# untitled.net
KiCad netlist of a schematic drawn in EAGLE
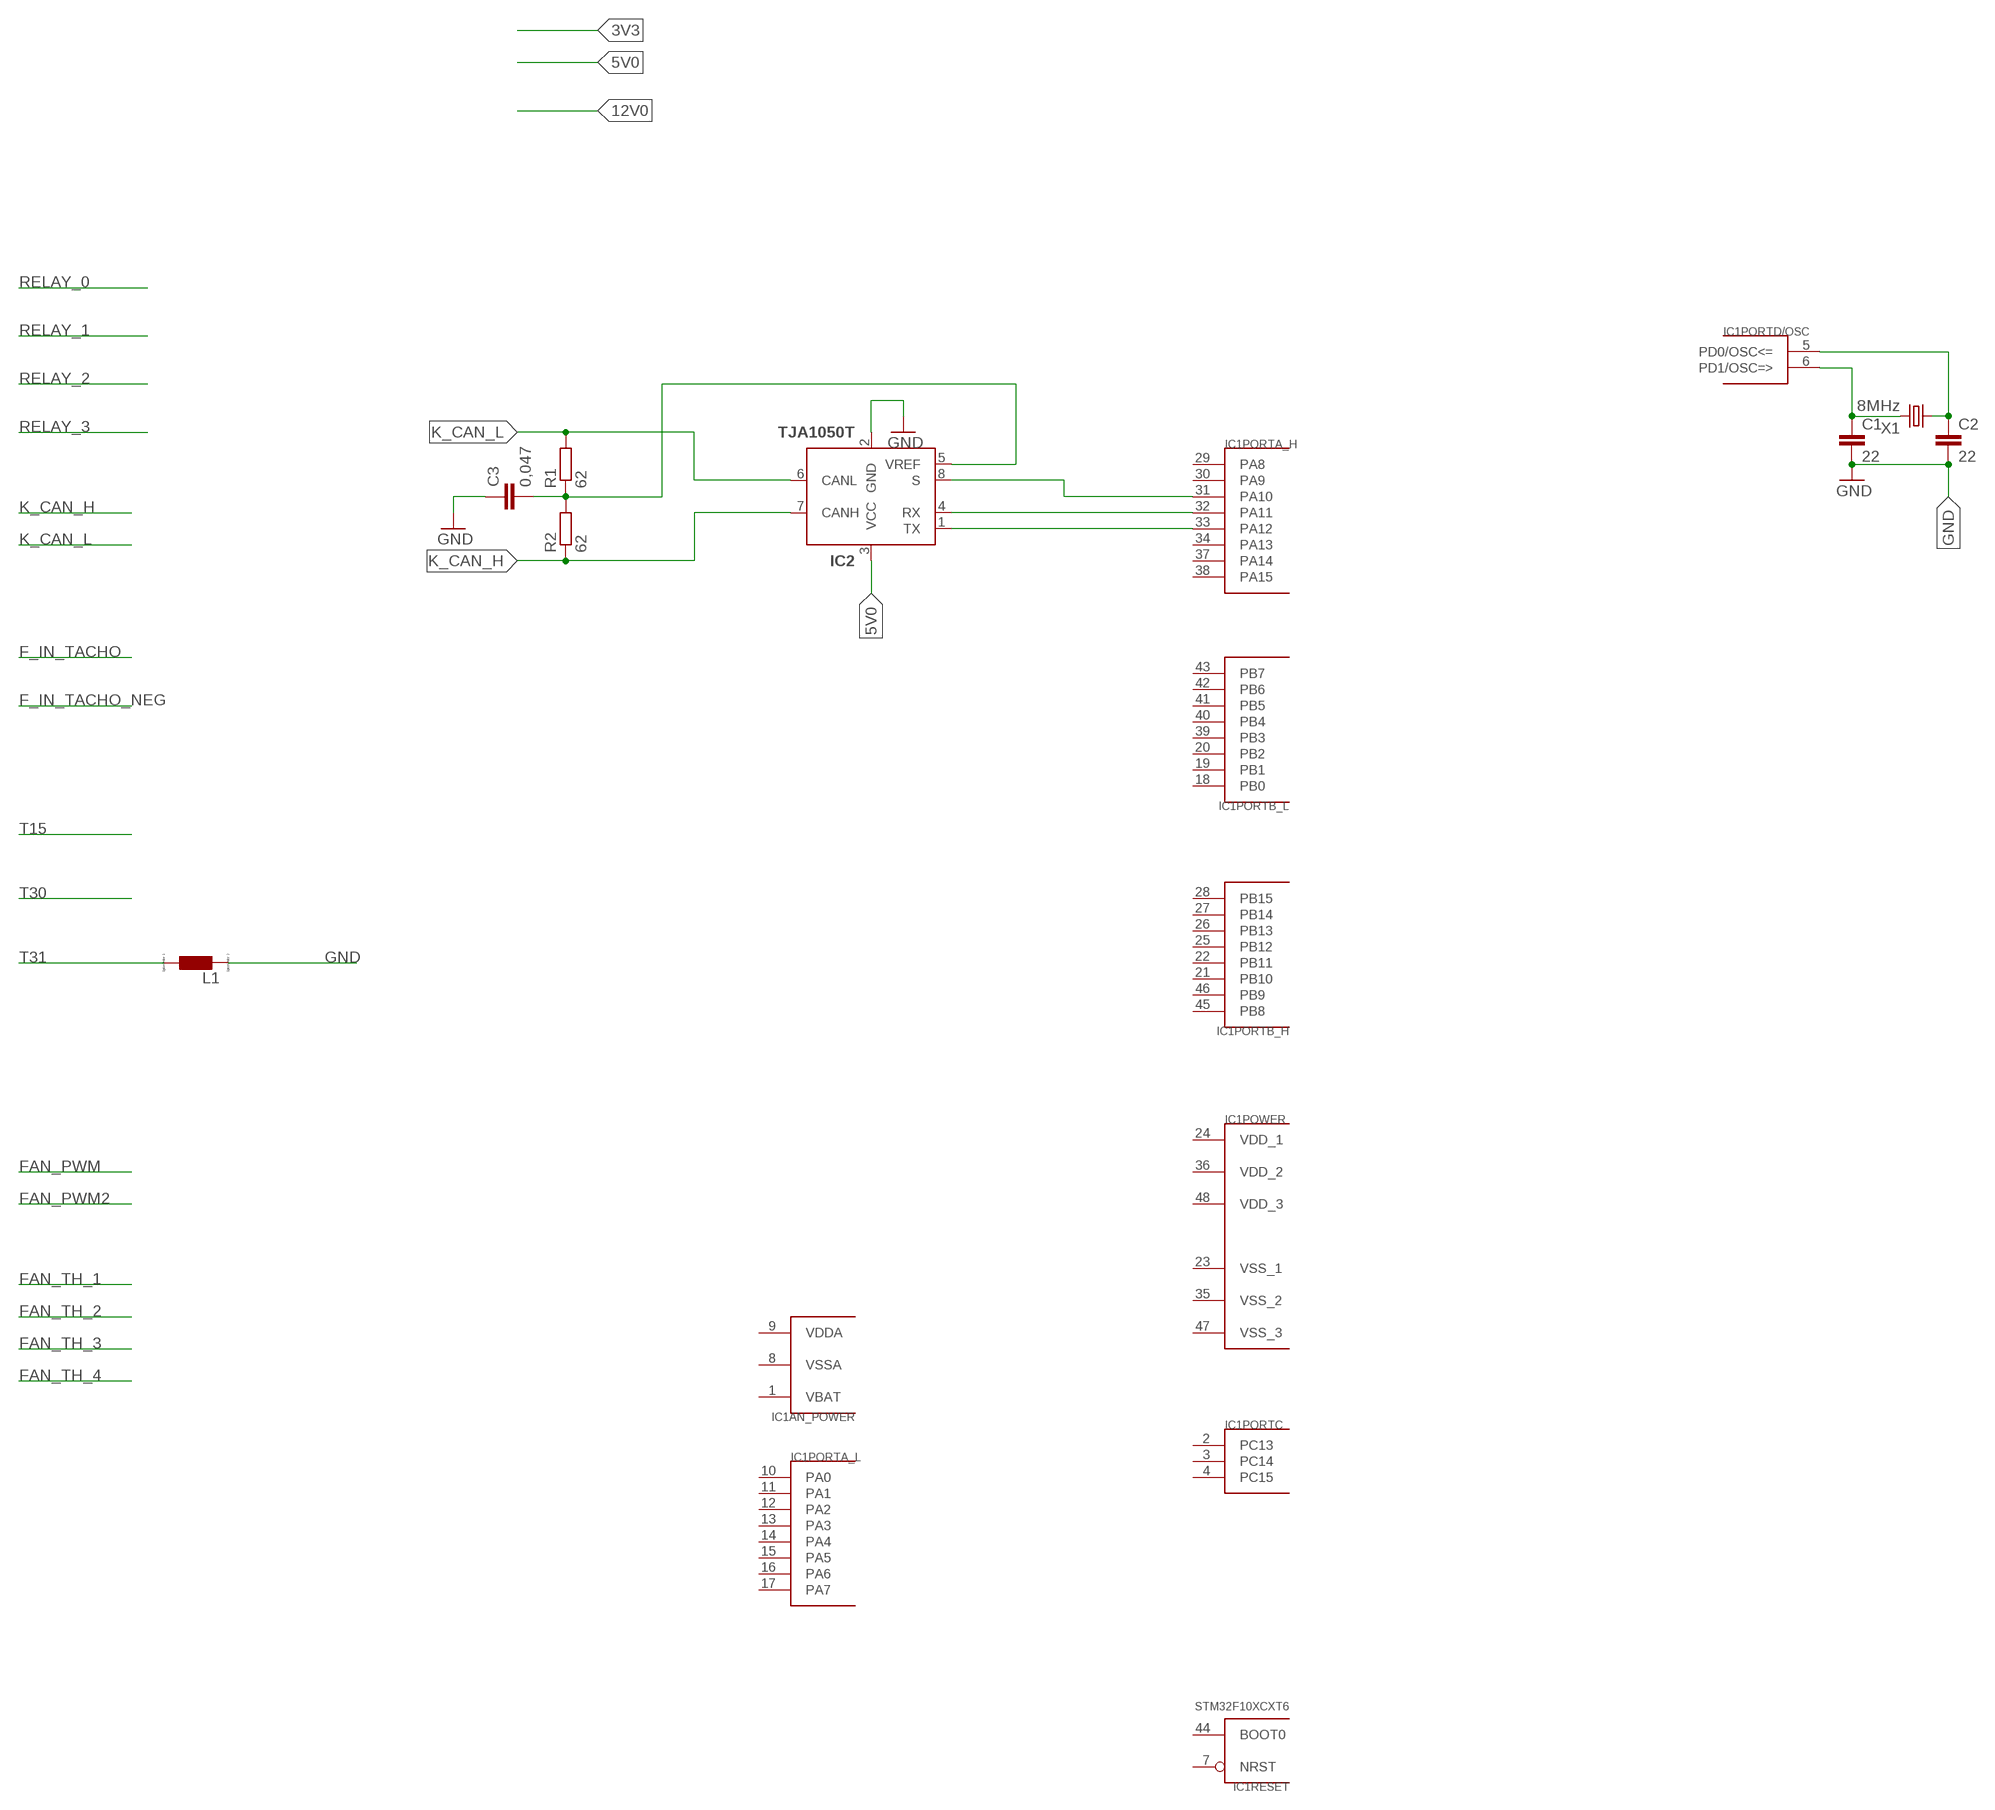
[diagram p0: schematic, sheet 1]

(export (version "E")
  (design (tool "Eeschema 10.0.6"))
  (components
    (comp (ref "C1")
      (value "22")
      (footprint "eagle-import:C0805")
      (libsource (lib "eagle-import") (part "C-EUC0805"))
    )
    (comp (ref "C2")
      (value "22")
      (footprint "eagle-import:C0805")
      (libsource (lib "eagle-import") (part "C-EUC0805"))
    )
    (comp (ref "C3")
      (value "0,047")
      (footprint "eagle-import:C0805")
      (libsource (lib "eagle-import") (part "C-EUC0805"))
    )
    (comp (ref "IC1")
      (value "STM32F10XCXT6")
      (footprint "eagle-import:TQFP48")
      (libsource (lib "eagle-import") (part "STM32F10XCXT6"))
    )
    (comp (ref "IC2")
      (value "TJA1050T")
      (footprint "eagle-import:SOIC8")
      (fields (field (name "MF") "NXP"))
      (libsource (lib "eagle-import") (part "TJA1050T"))
    )
    (comp (ref "L1")
      (value "L0204/7")
      (footprint "eagle-import:0204_7")
      (libsource (lib "eagle-import") (part "L0204/7"))
    )
    (comp (ref "R1")
      (value "62")
      (footprint "eagle-import:M0805")
      (libsource (lib "eagle-import") (part "R-EU_M0805"))
    )
    (comp (ref "R2")
      (value "62")
      (footprint "eagle-import:M0805")
      (libsource (lib "eagle-import") (part "R-EU_M0805"))
    )
    (comp (ref "X1")
      (value "8MHz")
      (footprint "eagle-import:HC49")
      (libsource (lib "eagle-import") (part "CRYSTALS-NOGND-HC49"))
    )
  )
  (nets
    (net (code "15") (name "/T31") (class "Default")
      (node (ref "L1") (pin "1") (pinfunction "1_1") (pintype "passive"))
    )
    (net (code "16") (name "/VBAT") (class "Default")
      (node (ref "IC1") (pin "1") (pinfunction "VBAT_1") (pintype "power_in"))
    )
    (net (code "17") (name "/VDDA") (class "Default")
      (node (ref "IC1") (pin "9") (pinfunction "VDDA_9") (pintype "power_in"))
    )
    (net (code "18") (name "/VDD_1") (class "Default")
      (node (ref "IC1") (pin "24") (pinfunction "VDD_1_24") (pintype "power_in"))
    )
    (net (code "19") (name "/VDD_2") (class "Default")
      (node (ref "IC1") (pin "36") (pinfunction "VDD_2_36") (pintype "power_in"))
    )
    (net (code "20") (name "/VDD_3") (class "Default")
      (node (ref "IC1") (pin "48") (pinfunction "VDD_3_48") (pintype "power_in"))
    )
    (net (code "21") (name "/VSSA") (class "Default")
      (node (ref "IC1") (pin "8") (pinfunction "VSSA_8") (pintype "power_in"))
    )
    (net (code "22") (name "/VSS_1") (class "Default")
      (node (ref "IC1") (pin "23") (pinfunction "VSS_1_23") (pintype "power_in"))
    )
    (net (code "23") (name "/VSS_2") (class "Default")
      (node (ref "IC1") (pin "35") (pinfunction "VSS_2_35") (pintype "power_in"))
    )
    (net (code "24") (name "/VSS_3") (class "Default")
      (node (ref "IC1") (pin "47") (pinfunction "VSS_3_47") (pintype "power_in"))
    )
    (net (code "26") (name "5V0") (class "Default")
      (node (ref "IC2") (pin "3") (pinfunction "VCC_3") (pintype "input"))
    )
    (net (code "28") (name "GND") (class "Default")
      (node (ref "C1") (pin "2") (pinfunction "2_2") (pintype "passive"))
      (node (ref "C2") (pin "2") (pinfunction "2_2") (pintype "passive"))
      (node (ref "C3") (pin "1") (pinfunction "1_1") (pintype "passive"))
      (node (ref "IC2") (pin "2") (pinfunction "GND_2") (pintype "power_in"))
      (node (ref "L1") (pin "2") (pinfunction "2_2") (pintype "passive"))
    )
    (net (code "29") (name "K_CAN_H") (class "Default")
      (node (ref "IC2") (pin "7") (pinfunction "CANH_7") (pintype "bidirectional"))
      (node (ref "R2") (pin "1") (pinfunction "1_1") (pintype "passive"))
    )
    (net (code "30") (name "K_CAN_L") (class "Default")
      (node (ref "IC2") (pin "6") (pinfunction "CANL_6") (pintype "bidirectional"))
      (node (ref "R1") (pin "2") (pinfunction "2_2") (pintype "passive"))
    )
    (net (code "31") (name "Net-(IC1B-PA10)") (class "Default")
      (node (ref "IC1") (pin "31") (pinfunction "PA10_31") (pintype "bidirectional"))
      (node (ref "IC2") (pin "8") (pinfunction "S_8") (pintype "input"))
    )
    (net (code "32") (name "Net-(IC1B-PA11)") (class "Default")
      (node (ref "IC1") (pin "32") (pinfunction "PA11_32") (pintype "bidirectional"))
      (node (ref "IC2") (pin "4") (pinfunction "RX_4") (pintype "output"))
    )
    (net (code "33") (name "Net-(IC1B-PA12)") (class "Default")
      (node (ref "IC1") (pin "33") (pinfunction "PA12_33") (pintype "bidirectional"))
      (node (ref "IC2") (pin "1") (pinfunction "TX_1") (pintype "input"))
    )
    (net (code "34") (name "Net-(IC1G-PD0{slash}OSC<=)") (class "Default")
      (node (ref "C2") (pin "1") (pinfunction "1_1") (pintype "passive"))
      (node (ref "IC1") (pin "5") (pinfunction "PD0/OSC<=_5") (pintype "bidirectional"))
      (node (ref "X1") (pin "1") (pinfunction "1_1") (pintype "passive"))
    )
    (net (code "35") (name "Net-(IC1G-PD1{slash}OSC=>)") (class "Default")
      (node (ref "C1") (pin "1") (pinfunction "1_1") (pintype "passive"))
      (node (ref "IC1") (pin "6") (pinfunction "PD1/OSC=>_6") (pintype "bidirectional"))
      (node (ref "X1") (pin "2") (pinfunction "2_2") (pintype "passive"))
    )
    (net (code "36") (name "Net-(IC2-VREF)") (class "Default")
      (node (ref "C3") (pin "2") (pinfunction "2_2") (pintype "passive"))
      (node (ref "IC2") (pin "5") (pinfunction "VREF_5") (pintype "output"))
      (node (ref "R1") (pin "1") (pinfunction "1_1") (pintype "passive"))
      (node (ref "R2") (pin "2") (pinfunction "2_2") (pintype "passive"))
    )
    (net (code "37") (name "unconnected-(IC1B-PA8-Pad29)") (class "Default")
      (node (ref "IC1") (pin "29") (pinfunction "PA8_29") (pintype "bidirectional"))
    )
    (net (code "38") (name "unconnected-(IC1B-PA9-Pad30)") (class "Default")
      (node (ref "IC1") (pin "30") (pinfunction "PA9_30") (pintype "bidirectional"))
    )
    (net (code "39") (name "unconnected-(IC1B-PA13-Pad34)") (class "Default")
      (node (ref "IC1") (pin "34") (pinfunction "PA13_34") (pintype "bidirectional"))
    )
    (net (code "40") (name "unconnected-(IC1B-PA14-Pad37)") (class "Default")
      (node (ref "IC1") (pin "37") (pinfunction "PA14_37") (pintype "bidirectional"))
    )
    (net (code "41") (name "unconnected-(IC1B-PA15-Pad38)") (class "Default")
      (node (ref "IC1") (pin "38") (pinfunction "PA15_38") (pintype "bidirectional"))
    )
    (net (code "42") (name "unconnected-(IC1C-PA0-Pad10)") (class "Default")
      (node (ref "IC1") (pin "10") (pinfunction "PA0_10") (pintype "bidirectional"))
    )
    (net (code "43") (name "unconnected-(IC1C-PA1-Pad11)") (class "Default")
      (node (ref "IC1") (pin "11") (pinfunction "PA1_11") (pintype "bidirectional"))
    )
    (net (code "44") (name "unconnected-(IC1C-PA2-Pad12)") (class "Default")
      (node (ref "IC1") (pin "12") (pinfunction "PA2_12") (pintype "bidirectional"))
    )
    (net (code "45") (name "unconnected-(IC1C-PA3-Pad13)") (class "Default")
      (node (ref "IC1") (pin "13") (pinfunction "PA3_13") (pintype "bidirectional"))
    )
    (net (code "46") (name "unconnected-(IC1C-PA4-Pad14)") (class "Default")
      (node (ref "IC1") (pin "14") (pinfunction "PA4_14") (pintype "bidirectional"))
    )
    (net (code "47") (name "unconnected-(IC1C-PA5-Pad15)") (class "Default")
      (node (ref "IC1") (pin "15") (pinfunction "PA5_15") (pintype "bidirectional"))
    )
    (net (code "48") (name "unconnected-(IC1C-PA6-Pad16)") (class "Default")
      (node (ref "IC1") (pin "16") (pinfunction "PA6_16") (pintype "bidirectional"))
    )
    (net (code "49") (name "unconnected-(IC1C-PA7-Pad17)") (class "Default")
      (node (ref "IC1") (pin "17") (pinfunction "PA7_17") (pintype "bidirectional"))
    )
    (net (code "50") (name "unconnected-(IC1D-PB8-Pad45)") (class "Default")
      (node (ref "IC1") (pin "45") (pinfunction "PB8_45") (pintype "bidirectional"))
    )
    (net (code "51") (name "unconnected-(IC1D-PB9-Pad46)") (class "Default")
      (node (ref "IC1") (pin "46") (pinfunction "PB9_46") (pintype "bidirectional"))
    )
    (net (code "52") (name "unconnected-(IC1D-PB10-Pad21)") (class "Default")
      (node (ref "IC1") (pin "21") (pinfunction "PB10_21") (pintype "bidirectional"))
    )
    (net (code "53") (name "unconnected-(IC1D-PB11-Pad22)") (class "Default")
      (node (ref "IC1") (pin "22") (pinfunction "PB11_22") (pintype "bidirectional"))
    )
    (net (code "54") (name "unconnected-(IC1D-PB12-Pad25)") (class "Default")
      (node (ref "IC1") (pin "25") (pinfunction "PB12_25") (pintype "bidirectional"))
    )
    (net (code "55") (name "unconnected-(IC1D-PB13-Pad26)") (class "Default")
      (node (ref "IC1") (pin "26") (pinfunction "PB13_26") (pintype "bidirectional"))
    )
    (net (code "56") (name "unconnected-(IC1D-PB14-Pad27)") (class "Default")
      (node (ref "IC1") (pin "27") (pinfunction "PB14_27") (pintype "bidirectional"))
    )
    (net (code "57") (name "unconnected-(IC1D-PB15-Pad28)") (class "Default")
      (node (ref "IC1") (pin "28") (pinfunction "PB15_28") (pintype "bidirectional"))
    )
    (net (code "58") (name "unconnected-(IC1E-PB0-Pad18)") (class "Default")
      (node (ref "IC1") (pin "18") (pinfunction "PB0_18") (pintype "bidirectional"))
    )
    (net (code "59") (name "unconnected-(IC1E-PB1-Pad19)") (class "Default")
      (node (ref "IC1") (pin "19") (pinfunction "PB1_19") (pintype "bidirectional"))
    )
    (net (code "60") (name "unconnected-(IC1E-PB2-Pad20)") (class "Default")
      (node (ref "IC1") (pin "20") (pinfunction "PB2_20") (pintype "bidirectional"))
    )
    (net (code "61") (name "unconnected-(IC1E-PB3-Pad39)") (class "Default")
      (node (ref "IC1") (pin "39") (pinfunction "PB3_39") (pintype "bidirectional"))
    )
    (net (code "62") (name "unconnected-(IC1E-PB4-Pad40)") (class "Default")
      (node (ref "IC1") (pin "40") (pinfunction "PB4_40") (pintype "bidirectional"))
    )
    (net (code "63") (name "unconnected-(IC1E-PB5-Pad41)") (class "Default")
      (node (ref "IC1") (pin "41") (pinfunction "PB5_41") (pintype "bidirectional"))
    )
    (net (code "64") (name "unconnected-(IC1E-PB6-Pad42)") (class "Default")
      (node (ref "IC1") (pin "42") (pinfunction "PB6_42") (pintype "bidirectional"))
    )
    (net (code "65") (name "unconnected-(IC1E-PB7-Pad43)") (class "Default")
      (node (ref "IC1") (pin "43") (pinfunction "PB7_43") (pintype "bidirectional"))
    )
    (net (code "66") (name "unconnected-(IC1F-PC13-Pad2)") (class "Default")
      (node (ref "IC1") (pin "2") (pinfunction "PC13_2") (pintype "bidirectional"))
    )
    (net (code "67") (name "unconnected-(IC1F-PC14-Pad3)") (class "Default")
      (node (ref "IC1") (pin "3") (pinfunction "PC14_3") (pintype "bidirectional"))
    )
    (net (code "68") (name "unconnected-(IC1F-PC15-Pad4)") (class "Default")
      (node (ref "IC1") (pin "4") (pinfunction "PC15_4") (pintype "bidirectional"))
    )
    (net (code "69") (name "unconnected-(IC1I-BOOT0-Pad44)") (class "Default")
      (node (ref "IC1") (pin "44") (pinfunction "BOOT0_44") (pintype "input"))
    )
    (net (code "70") (name "unconnected-(IC1I-NRST-Pad7)") (class "Default")
      (node (ref "IC1") (pin "7") (pinfunction "NRST_7") (pintype "input"))
    )
  )
)
